# Nano_C1101.net
KiCad netlist of a schematic drawn in EAGLE
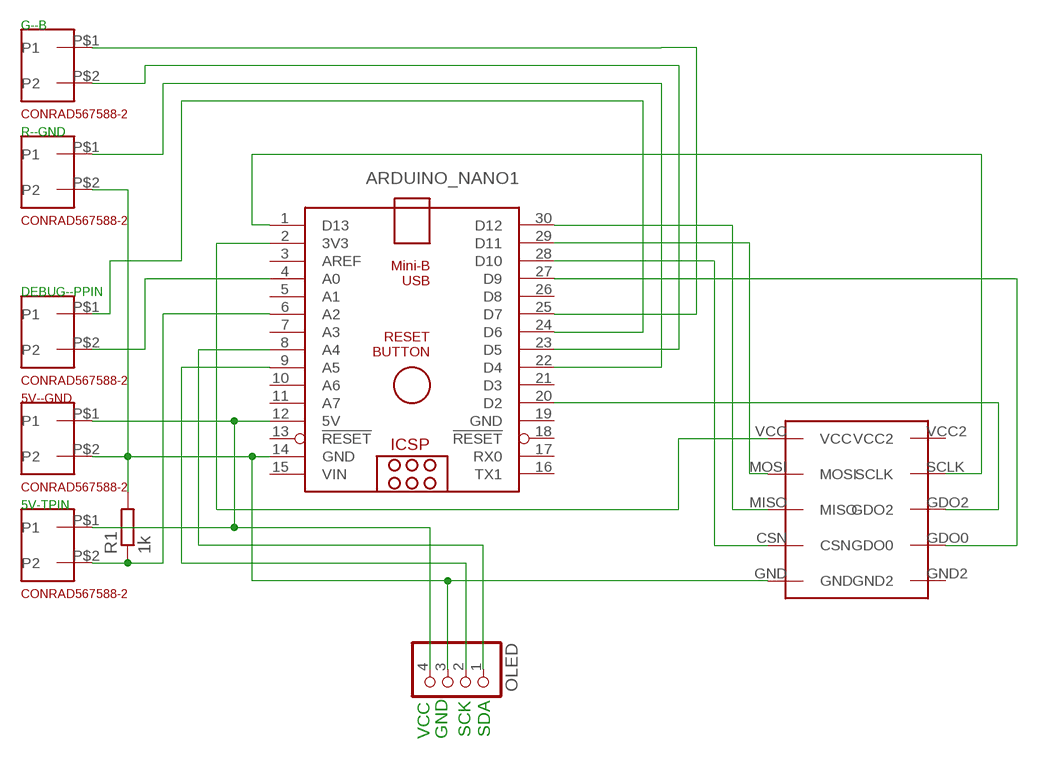
[diagram p0: schematic, sheet 1]

(export (version "E")
  (design (tool "Eeschema 10.0.6"))
  (components
    (comp (ref "5V--GND")
      (value "CONRAD567588-2")
      (footprint "eagle-import:CONRAD567588")
      (libsource (lib "eagle-import") (part "CONRAD567588-2"))
    )
    (comp (ref "5V-TPIN")
      (value "CONRAD567588-2")
      (footprint "eagle-import:CONRAD567588")
      (libsource (lib "eagle-import") (part "CONRAD567588-2"))
    )
    (comp (ref "ARDUINO_NANO1")
      (value "ARDUINO_NANO")
      (footprint "eagle-import:ARDUINO_NANO")
      (libsource (lib "eagle-import") (part "ARDUINO_NANO"))
    )
    (comp (ref "DEBUG--PPIN")
      (value "CONRAD567588-2")
      (footprint "eagle-import:CONRAD567588")
      (libsource (lib "eagle-import") (part "CONRAD567588-2"))
    )
    (comp (ref "G--B")
      (value "CONRAD567588-2")
      (footprint "eagle-import:CONRAD567588")
      (libsource (lib "eagle-import") (part "CONRAD567588-2"))
    )
    (comp (ref "OLED")
      (value "PINHD-1X4")
      (footprint "eagle-import:1X04")
      (libsource (lib "eagle-import") (part "PINHD-1X4"))
    )
    (comp (ref "R--GND")
      (value "CONRAD567588-2")
      (footprint "eagle-import:CONRAD567588")
      (libsource (lib "eagle-import") (part "CONRAD567588-2"))
    )
    (comp (ref "R1")
      (value "1k")
      (footprint "eagle-import:0204_7")
      (libsource (lib "eagle-import") (part "R-EU_0204/7"))
    )
    (comp (ref "U$1")
      (value "NEUFTECH_CC1101")
      (footprint "eagle-import:NEUFTECH_CC1101_PACKAGE")
      (libsource (lib "eagle-import") (part "NEUFTECH_CC1101"))
    )
  )
  (nets
    (net (code "1") (name "/GND") (class "Default")
      (node (ref "ARDUINO_NANO1") (pin "19") (pinfunction "GND_19") (pintype "power_in"))
    )
    (net (code "2") (name "/VIN") (class "Default")
      (node (ref "ARDUINO_NANO1") (pin "15") (pinfunction "VIN_15") (pintype "power_in"))
    )
    (net (code "3") (name "Net-(5V--GND-P1)") (class "Default")
      (node (ref "5V--GND") (pin "P$1") (pinfunction "P1_P$1") (pintype "bidirectional"))
      (node (ref "5V-TPIN") (pin "P$1") (pinfunction "P1_P$1") (pintype "bidirectional"))
      (node (ref "ARDUINO_NANO1") (pin "12") (pinfunction "5V_12") (pintype "power_in"))
      (node (ref "OLED") (pin "4") (pinfunction "4_4") (pintype "passive"))
    )
    (net (code "4") (name "Net-(5V--GND-P2)") (class "Default")
      (node (ref "5V--GND") (pin "P$2") (pinfunction "P2_P$2") (pintype "bidirectional"))
      (node (ref "ARDUINO_NANO1") (pin "14") (pinfunction "GND_14") (pintype "power_in"))
      (node (ref "OLED") (pin "3") (pinfunction "3_3") (pintype "passive"))
      (node (ref "R--GND") (pin "P$2") (pinfunction "P2_P$2") (pintype "bidirectional"))
      (node (ref "R1") (pin "2") (pinfunction "2_2") (pintype "passive"))
      (node (ref "U$1") (pin "GND") (pinfunction "GND_GND") (pintype "bidirectional"))
    )
    (net (code "5") (name "Net-(5V-TPIN-P2)") (class "Default")
      (node (ref "5V-TPIN") (pin "P$2") (pinfunction "P2_P$2") (pintype "bidirectional"))
      (node (ref "ARDUINO_NANO1") (pin "6") (pinfunction "A2_6") (pintype "bidirectional"))
      (node (ref "R1") (pin "1") (pinfunction "1_1") (pintype "passive"))
    )
    (net (code "6") (name "Net-(ARDUINO_NANO1-3V3)") (class "Default")
      (node (ref "ARDUINO_NANO1") (pin "2") (pinfunction "3V3_2") (pintype "output"))
      (node (ref "U$1") (pin "VCC") (pinfunction "VCC_VCC") (pintype "bidirectional"))
    )
    (net (code "7") (name "Net-(ARDUINO_NANO1-A0)") (class "Default")
      (node (ref "ARDUINO_NANO1") (pin "4") (pinfunction "A0_4") (pintype "bidirectional"))
      (node (ref "DEBUG--PPIN") (pin "P$2") (pinfunction "P2_P$2") (pintype "bidirectional"))
    )
    (net (code "8") (name "Net-(ARDUINO_NANO1-A4)") (class "Default")
      (node (ref "ARDUINO_NANO1") (pin "8") (pinfunction "A4_8") (pintype "bidirectional"))
      (node (ref "OLED") (pin "1") (pinfunction "1_1") (pintype "passive"))
    )
    (net (code "9") (name "Net-(ARDUINO_NANO1-A5)") (class "Default")
      (node (ref "ARDUINO_NANO1") (pin "9") (pinfunction "A5_9") (pintype "bidirectional"))
      (node (ref "OLED") (pin "2") (pinfunction "2_2") (pintype "passive"))
    )
    (net (code "10") (name "Net-(ARDUINO_NANO1-D2)") (class "Default")
      (node (ref "ARDUINO_NANO1") (pin "20") (pinfunction "D2_20") (pintype "bidirectional"))
      (node (ref "U$1") (pin "GDO2") (pinfunction "GDO2_GDO2") (pintype "bidirectional"))
    )
    (net (code "11") (name "Net-(ARDUINO_NANO1-D4)") (class "Default")
      (node (ref "ARDUINO_NANO1") (pin "22") (pinfunction "D4_22") (pintype "bidirectional"))
      (node (ref "R--GND") (pin "P$1") (pinfunction "P1_P$1") (pintype "bidirectional"))
    )
    (net (code "12") (name "Net-(ARDUINO_NANO1-D5)") (class "Default")
      (node (ref "ARDUINO_NANO1") (pin "23") (pinfunction "D5_23") (pintype "bidirectional"))
      (node (ref "G--B") (pin "P$2") (pinfunction "P2_P$2") (pintype "bidirectional"))
    )
    (net (code "13") (name "Net-(ARDUINO_NANO1-D6)") (class "Default")
      (node (ref "ARDUINO_NANO1") (pin "24") (pinfunction "D6_24") (pintype "bidirectional"))
      (node (ref "DEBUG--PPIN") (pin "P$1") (pinfunction "P1_P$1") (pintype "bidirectional"))
    )
    (net (code "14") (name "Net-(ARDUINO_NANO1-D7)") (class "Default")
      (node (ref "ARDUINO_NANO1") (pin "25") (pinfunction "D7_25") (pintype "bidirectional"))
      (node (ref "G--B") (pin "P$1") (pinfunction "P1_P$1") (pintype "bidirectional"))
    )
    (net (code "15") (name "Net-(ARDUINO_NANO1-D9)") (class "Default")
      (node (ref "ARDUINO_NANO1") (pin "27") (pinfunction "D9_27") (pintype "bidirectional"))
      (node (ref "U$1") (pin "GDO0") (pinfunction "GDO0_GDO0") (pintype "bidirectional"))
    )
    (net (code "16") (name "Net-(ARDUINO_NANO1-D10)") (class "Default")
      (node (ref "ARDUINO_NANO1") (pin "28") (pinfunction "D10_28") (pintype "bidirectional"))
      (node (ref "U$1") (pin "CSN") (pinfunction "CSN_CSN") (pintype "bidirectional"))
    )
    (net (code "17") (name "Net-(ARDUINO_NANO1-D11)") (class "Default")
      (node (ref "ARDUINO_NANO1") (pin "29") (pinfunction "D11_29") (pintype "bidirectional"))
      (node (ref "U$1") (pin "MOSI") (pinfunction "MOSI_MOSI") (pintype "bidirectional"))
    )
    (net (code "18") (name "Net-(ARDUINO_NANO1-D12)") (class "Default")
      (node (ref "ARDUINO_NANO1") (pin "30") (pinfunction "D12_30") (pintype "bidirectional"))
      (node (ref "U$1") (pin "MISO") (pinfunction "MISO_MISO") (pintype "bidirectional"))
    )
    (net (code "19") (name "Net-(ARDUINO_NANO1-D13)") (class "Default")
      (node (ref "ARDUINO_NANO1") (pin "1") (pinfunction "D13_1") (pintype "bidirectional"))
      (node (ref "U$1") (pin "SCLK") (pinfunction "SCLK_SCLK") (pintype "bidirectional"))
    )
    (net (code "20") (name "unconnected-(ARDUINO_NANO1-A1-Pad5)") (class "Default")
      (node (ref "ARDUINO_NANO1") (pin "5") (pinfunction "A1_5") (pintype "bidirectional"))
    )
    (net (code "21") (name "unconnected-(ARDUINO_NANO1-A3-Pad7)") (class "Default")
      (node (ref "ARDUINO_NANO1") (pin "7") (pinfunction "A3_7") (pintype "bidirectional"))
    )
    (net (code "22") (name "unconnected-(ARDUINO_NANO1-A6-Pad10)") (class "Default")
      (node (ref "ARDUINO_NANO1") (pin "10") (pinfunction "A6_10") (pintype "bidirectional"))
    )
    (net (code "23") (name "unconnected-(ARDUINO_NANO1-A7-Pad11)") (class "Default")
      (node (ref "ARDUINO_NANO1") (pin "11") (pinfunction "A7_11") (pintype "bidirectional"))
    )
    (net (code "24") (name "unconnected-(ARDUINO_NANO1-AREF-Pad3)") (class "Default")
      (node (ref "ARDUINO_NANO1") (pin "3") (pinfunction "AREF_3") (pintype "input"))
    )
    (net (code "25") (name "unconnected-(ARDUINO_NANO1-D3-Pad21)") (class "Default")
      (node (ref "ARDUINO_NANO1") (pin "21") (pinfunction "D3_21") (pintype "bidirectional"))
    )
    (net (code "26") (name "unconnected-(ARDUINO_NANO1-D8-Pad26)") (class "Default")
      (node (ref "ARDUINO_NANO1") (pin "26") (pinfunction "D8_26") (pintype "bidirectional"))
    )
    (net (code "27") (name "unconnected-(ARDUINO_NANO1-RX0-Pad17)") (class "Default")
      (node (ref "ARDUINO_NANO1") (pin "17") (pinfunction "RX0_17") (pintype "bidirectional"))
    )
    (net (code "28") (name "unconnected-(ARDUINO_NANO1-TX1-Pad16)") (class "Default")
      (node (ref "ARDUINO_NANO1") (pin "16") (pinfunction "TX1_16") (pintype "bidirectional"))
    )
    (net (code "29") (name "unconnected-(ARDUINO_NANO1-~{RESET}-Pad13)") (class "Default")
      (node (ref "ARDUINO_NANO1") (pin "13") (pinfunction "~{RESET}_13") (pintype "input"))
    )
    (net (code "30") (name "unconnected-(ARDUINO_NANO1-~{RESET}-Pad18)") (class "Default")
      (node (ref "ARDUINO_NANO1") (pin "18") (pinfunction "~{RESET}_18") (pintype "input"))
    )
    (net (code "31") (name "unconnected-(U$1-PadGND2)") (class "Default")
      (node (ref "U$1") (pin "GND2") (pinfunction "GND2_GND2") (pintype "bidirectional"))
    )
    (net (code "32") (name "unconnected-(U$1-PadVCC2)") (class "Default")
      (node (ref "U$1") (pin "VCC2") (pinfunction "VCC2_VCC2") (pintype "bidirectional"))
    )
  )
)
